# amebot_sensores.net
KiCad netlist of a schematic drawn in EAGLE
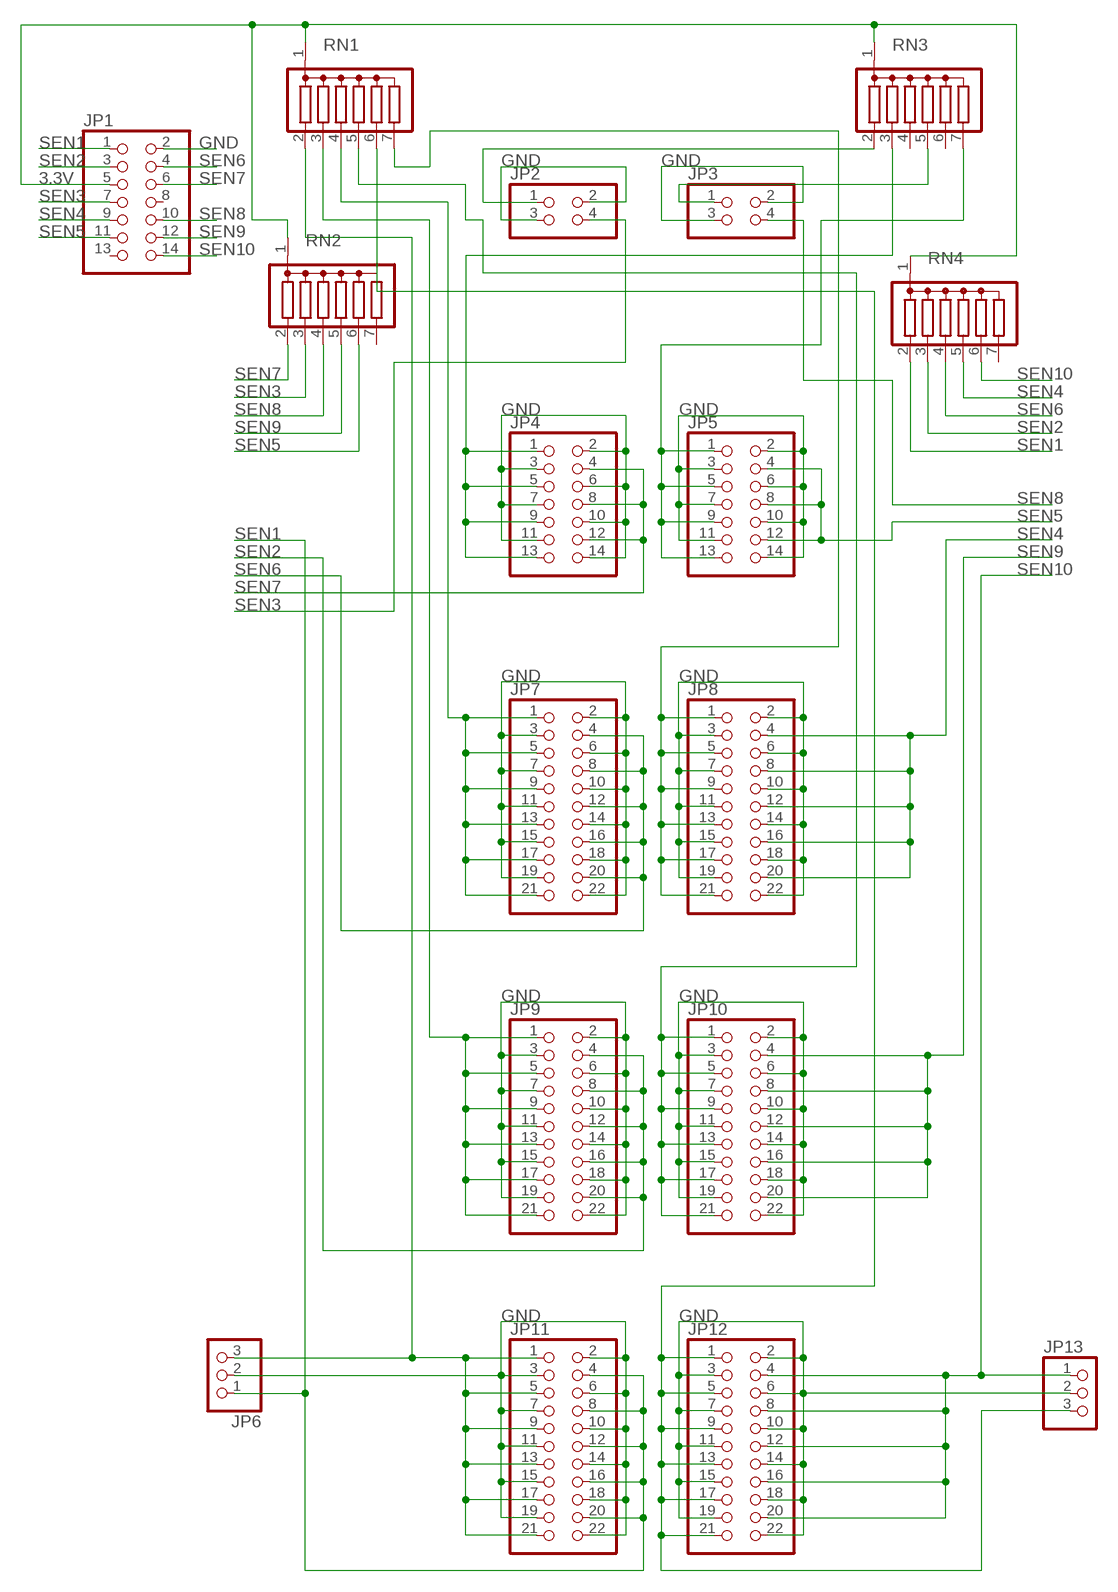
[diagram p0: schematic, sheet 1]

(export (version "E")
  (design (tool "Eeschema 10.0.6"))
  (components
    (comp (ref "JP1")
      (value "PINHD-2X7")
      (footprint "eagle-import:2X07")
      (libsource (lib "eagle-import") (part "PINHD-2X7"))
    )
    (comp (ref "JP2")
      (value "PINHD-2X2")
      (footprint "eagle-import:2X02")
      (libsource (lib "eagle-import") (part "PINHD-2X2"))
    )
    (comp (ref "JP3")
      (value "PINHD-2X2")
      (footprint "eagle-import:2X02")
      (libsource (lib "eagle-import") (part "PINHD-2X2"))
    )
    (comp (ref "JP4")
      (value "PINHD-2X7")
      (footprint "eagle-import:2X07")
      (libsource (lib "eagle-import") (part "PINHD-2X7"))
    )
    (comp (ref "JP5")
      (value "PINHD-2X7")
      (footprint "eagle-import:2X07")
      (libsource (lib "eagle-import") (part "PINHD-2X7"))
    )
    (comp (ref "JP6")
      (value "PINHD-1X3")
      (footprint "eagle-import:1X03")
      (libsource (lib "eagle-import") (part "PINHD-1X3"))
    )
    (comp (ref "JP7")
      (value "PINHD-2X11")
      (footprint "eagle-import:2X11")
      (libsource (lib "eagle-import") (part "PINHD-2X11"))
    )
    (comp (ref "JP8")
      (value "PINHD-2X11")
      (footprint "eagle-import:2X11")
      (libsource (lib "eagle-import") (part "PINHD-2X11"))
    )
    (comp (ref "JP9")
      (value "PINHD-2X11")
      (footprint "eagle-import:2X11")
      (libsource (lib "eagle-import") (part "PINHD-2X11"))
    )
    (comp (ref "JP10")
      (value "PINHD-2X11")
      (footprint "eagle-import:2X11")
      (libsource (lib "eagle-import") (part "PINHD-2X11"))
    )
    (comp (ref "JP11")
      (value "PINHD-2X11")
      (footprint "eagle-import:2X11")
      (libsource (lib "eagle-import") (part "PINHD-2X11"))
    )
    (comp (ref "JP12")
      (value "PINHD-2X11")
      (footprint "eagle-import:2X11")
      (libsource (lib "eagle-import") (part "PINHD-2X11"))
    )
    (comp (ref "JP13")
      (value "PINHD-1X3")
      (footprint "eagle-import:1X03")
      (libsource (lib "eagle-import") (part "PINHD-1X3"))
    )
    (comp (ref "RN1")
      (value "G06R")
      (footprint "eagle-import:SIL7")
      (libsource (lib "eagle-import") (part "G06R"))
    )
    (comp (ref "RN2")
      (value "G06R")
      (footprint "eagle-import:SIL7")
      (libsource (lib "eagle-import") (part "G06R"))
    )
    (comp (ref "RN3")
      (value "G06R")
      (footprint "eagle-import:SIL7")
      (libsource (lib "eagle-import") (part "G06R"))
    )
    (comp (ref "RN4")
      (value "G06R")
      (footprint "eagle-import:SIL7")
      (libsource (lib "eagle-import") (part "G06R"))
    )
  )
  (nets
    (net (code "1") (name "/3.3V") (class "Default")
      (node (ref "JP1") (pin "5") (pinfunction "5_5") (pintype "passive"))
      (node (ref "RN1") (pin "1") (pinfunction "1_1") (pintype "passive"))
      (node (ref "RN2") (pin "1") (pinfunction "1_1") (pintype "passive"))
      (node (ref "RN3") (pin "1") (pinfunction "1_1") (pintype "passive"))
      (node (ref "RN4") (pin "1") (pinfunction "1_1") (pintype "passive"))
    )
    (net (code "2") (name "/GND") (class "Default")
      (node (ref "JP1") (pin "2") (pinfunction "2_2") (pintype "passive"))
      (node (ref "JP10") (pin "10") (pinfunction "10_10") (pintype "passive"))
      (node (ref "JP10") (pin "11") (pinfunction "11_11") (pintype "passive"))
      (node (ref "JP10") (pin "14") (pinfunction "14_14") (pintype "passive"))
      (node (ref "JP10") (pin "15") (pinfunction "15_15") (pintype "passive"))
      (node (ref "JP10") (pin "18") (pinfunction "18_18") (pintype "passive"))
      (node (ref "JP10") (pin "19") (pinfunction "19_19") (pintype "passive"))
      (node (ref "JP10") (pin "2") (pinfunction "2_2") (pintype "passive"))
      (node (ref "JP10") (pin "22") (pinfunction "22_22") (pintype "passive"))
      (node (ref "JP10") (pin "3") (pinfunction "3_3") (pintype "passive"))
      (node (ref "JP10") (pin "6") (pinfunction "6_6") (pintype "passive"))
      (node (ref "JP10") (pin "7") (pinfunction "7_7") (pintype "passive"))
      (node (ref "JP11") (pin "10") (pinfunction "10_10") (pintype "passive"))
      (node (ref "JP11") (pin "11") (pinfunction "11_11") (pintype "passive"))
      (node (ref "JP11") (pin "14") (pinfunction "14_14") (pintype "passive"))
      (node (ref "JP11") (pin "15") (pinfunction "15_15") (pintype "passive"))
      (node (ref "JP11") (pin "18") (pinfunction "18_18") (pintype "passive"))
      (node (ref "JP11") (pin "19") (pinfunction "19_19") (pintype "passive"))
      (node (ref "JP11") (pin "2") (pinfunction "2_2") (pintype "passive"))
      (node (ref "JP11") (pin "22") (pinfunction "22_22") (pintype "passive"))
      (node (ref "JP11") (pin "3") (pinfunction "3_3") (pintype "passive"))
      (node (ref "JP11") (pin "6") (pinfunction "6_6") (pintype "passive"))
      (node (ref "JP11") (pin "7") (pinfunction "7_7") (pintype "passive"))
      (node (ref "JP12") (pin "10") (pinfunction "10_10") (pintype "passive"))
      (node (ref "JP12") (pin "11") (pinfunction "11_11") (pintype "passive"))
      (node (ref "JP12") (pin "14") (pinfunction "14_14") (pintype "passive"))
      (node (ref "JP12") (pin "15") (pinfunction "15_15") (pintype "passive"))
      (node (ref "JP12") (pin "18") (pinfunction "18_18") (pintype "passive"))
      (node (ref "JP12") (pin "19") (pinfunction "19_19") (pintype "passive"))
      (node (ref "JP12") (pin "2") (pinfunction "2_2") (pintype "passive"))
      (node (ref "JP12") (pin "22") (pinfunction "22_22") (pintype "passive"))
      (node (ref "JP12") (pin "3") (pinfunction "3_3") (pintype "passive"))
      (node (ref "JP12") (pin "6") (pinfunction "6_6") (pintype "passive"))
      (node (ref "JP12") (pin "7") (pinfunction "7_7") (pintype "passive"))
      (node (ref "JP13") (pin "2") (pinfunction "2_2") (pintype "passive"))
      (node (ref "JP2") (pin "2") (pinfunction "2_2") (pintype "passive"))
      (node (ref "JP2") (pin "3") (pinfunction "3_3") (pintype "passive"))
      (node (ref "JP3") (pin "2") (pinfunction "2_2") (pintype "passive"))
      (node (ref "JP3") (pin "3") (pinfunction "3_3") (pintype "passive"))
      (node (ref "JP4") (pin "10") (pinfunction "10_10") (pintype "passive"))
      (node (ref "JP4") (pin "11") (pinfunction "11_11") (pintype "passive"))
      (node (ref "JP4") (pin "14") (pinfunction "14_14") (pintype "passive"))
      (node (ref "JP4") (pin "2") (pinfunction "2_2") (pintype "passive"))
      (node (ref "JP4") (pin "3") (pinfunction "3_3") (pintype "passive"))
      (node (ref "JP4") (pin "6") (pinfunction "6_6") (pintype "passive"))
      (node (ref "JP4") (pin "7") (pinfunction "7_7") (pintype "passive"))
      (node (ref "JP5") (pin "10") (pinfunction "10_10") (pintype "passive"))
      (node (ref "JP5") (pin "11") (pinfunction "11_11") (pintype "passive"))
      (node (ref "JP5") (pin "14") (pinfunction "14_14") (pintype "passive"))
      (node (ref "JP5") (pin "2") (pinfunction "2_2") (pintype "passive"))
      (node (ref "JP5") (pin "3") (pinfunction "3_3") (pintype "passive"))
      (node (ref "JP5") (pin "6") (pinfunction "6_6") (pintype "passive"))
      (node (ref "JP5") (pin "7") (pinfunction "7_7") (pintype "passive"))
      (node (ref "JP6") (pin "2") (pinfunction "2_2") (pintype "passive"))
      (node (ref "JP7") (pin "10") (pinfunction "10_10") (pintype "passive"))
      (node (ref "JP7") (pin "11") (pinfunction "11_11") (pintype "passive"))
      (node (ref "JP7") (pin "14") (pinfunction "14_14") (pintype "passive"))
      (node (ref "JP7") (pin "15") (pinfunction "15_15") (pintype "passive"))
      (node (ref "JP7") (pin "18") (pinfunction "18_18") (pintype "passive"))
      (node (ref "JP7") (pin "19") (pinfunction "19_19") (pintype "passive"))
      (node (ref "JP7") (pin "2") (pinfunction "2_2") (pintype "passive"))
      (node (ref "JP7") (pin "22") (pinfunction "22_22") (pintype "passive"))
      (node (ref "JP7") (pin "3") (pinfunction "3_3") (pintype "passive"))
      (node (ref "JP7") (pin "6") (pinfunction "6_6") (pintype "passive"))
      (node (ref "JP7") (pin "7") (pinfunction "7_7") (pintype "passive"))
      (node (ref "JP8") (pin "10") (pinfunction "10_10") (pintype "passive"))
      (node (ref "JP8") (pin "11") (pinfunction "11_11") (pintype "passive"))
      (node (ref "JP8") (pin "14") (pinfunction "14_14") (pintype "passive"))
      (node (ref "JP8") (pin "15") (pinfunction "15_15") (pintype "passive"))
      (node (ref "JP8") (pin "18") (pinfunction "18_18") (pintype "passive"))
      (node (ref "JP8") (pin "19") (pinfunction "19_19") (pintype "passive"))
      (node (ref "JP8") (pin "2") (pinfunction "2_2") (pintype "passive"))
      (node (ref "JP8") (pin "22") (pinfunction "22_22") (pintype "passive"))
      (node (ref "JP8") (pin "3") (pinfunction "3_3") (pintype "passive"))
      (node (ref "JP8") (pin "6") (pinfunction "6_6") (pintype "passive"))
      (node (ref "JP8") (pin "7") (pinfunction "7_7") (pintype "passive"))
      (node (ref "JP9") (pin "10") (pinfunction "10_10") (pintype "passive"))
      (node (ref "JP9") (pin "11") (pinfunction "11_11") (pintype "passive"))
      (node (ref "JP9") (pin "14") (pinfunction "14_14") (pintype "passive"))
      (node (ref "JP9") (pin "15") (pinfunction "15_15") (pintype "passive"))
      (node (ref "JP9") (pin "18") (pinfunction "18_18") (pintype "passive"))
      (node (ref "JP9") (pin "19") (pinfunction "19_19") (pintype "passive"))
      (node (ref "JP9") (pin "2") (pinfunction "2_2") (pintype "passive"))
      (node (ref "JP9") (pin "22") (pinfunction "22_22") (pintype "passive"))
      (node (ref "JP9") (pin "3") (pinfunction "3_3") (pintype "passive"))
      (node (ref "JP9") (pin "6") (pinfunction "6_6") (pintype "passive"))
      (node (ref "JP9") (pin "7") (pinfunction "7_7") (pintype "passive"))
    )
    (net (code "3") (name "/SEN1") (class "Default")
      (node (ref "JP1") (pin "1") (pinfunction "1_1") (pintype "passive"))
      (node (ref "JP11") (pin "12") (pinfunction "12_12") (pintype "passive"))
      (node (ref "JP11") (pin "16") (pinfunction "16_16") (pintype "passive"))
      (node (ref "JP11") (pin "20") (pinfunction "20_20") (pintype "passive"))
      (node (ref "JP11") (pin "4") (pinfunction "4_4") (pintype "passive"))
      (node (ref "JP11") (pin "8") (pinfunction "8_8") (pintype "passive"))
      (node (ref "JP6") (pin "1") (pinfunction "1_1") (pintype "passive"))
      (node (ref "RN4") (pin "2") (pinfunction "2_2") (pintype "passive"))
    )
    (net (code "4") (name "/SEN2") (class "Default")
      (node (ref "JP1") (pin "3") (pinfunction "3_3") (pintype "passive"))
      (node (ref "JP9") (pin "12") (pinfunction "12_12") (pintype "passive"))
      (node (ref "JP9") (pin "16") (pinfunction "16_16") (pintype "passive"))
      (node (ref "JP9") (pin "20") (pinfunction "20_20") (pintype "passive"))
      (node (ref "JP9") (pin "4") (pinfunction "4_4") (pintype "passive"))
      (node (ref "JP9") (pin "8") (pinfunction "8_8") (pintype "passive"))
      (node (ref "RN4") (pin "3") (pinfunction "3_3") (pintype "passive"))
    )
    (net (code "5") (name "/SEN3") (class "Default")
      (node (ref "JP1") (pin "7") (pinfunction "7_7") (pintype "passive"))
      (node (ref "JP2") (pin "4") (pinfunction "4_4") (pintype "passive"))
      (node (ref "RN2") (pin "3") (pinfunction "3_3") (pintype "passive"))
    )
    (net (code "6") (name "/SEN4") (class "Default")
      (node (ref "JP1") (pin "9") (pinfunction "9_9") (pintype "passive"))
      (node (ref "JP8") (pin "12") (pinfunction "12_12") (pintype "passive"))
      (node (ref "JP8") (pin "16") (pinfunction "16_16") (pintype "passive"))
      (node (ref "JP8") (pin "20") (pinfunction "20_20") (pintype "passive"))
      (node (ref "JP8") (pin "4") (pinfunction "4_4") (pintype "passive"))
      (node (ref "JP8") (pin "8") (pinfunction "8_8") (pintype "passive"))
      (node (ref "RN4") (pin "5") (pinfunction "5_5") (pintype "passive"))
    )
    (net (code "7") (name "/SEN5") (class "Default")
      (node (ref "JP1") (pin "11") (pinfunction "11_11") (pintype "passive"))
      (node (ref "JP5") (pin "12") (pinfunction "12_12") (pintype "passive"))
      (node (ref "JP5") (pin "4") (pinfunction "4_4") (pintype "passive"))
      (node (ref "JP5") (pin "8") (pinfunction "8_8") (pintype "passive"))
      (node (ref "RN2") (pin "6") (pinfunction "6_6") (pintype "passive"))
    )
    (net (code "8") (name "/SEN6") (class "Default")
      (node (ref "JP1") (pin "4") (pinfunction "4_4") (pintype "passive"))
      (node (ref "JP7") (pin "12") (pinfunction "12_12") (pintype "passive"))
      (node (ref "JP7") (pin "16") (pinfunction "16_16") (pintype "passive"))
      (node (ref "JP7") (pin "20") (pinfunction "20_20") (pintype "passive"))
      (node (ref "JP7") (pin "4") (pinfunction "4_4") (pintype "passive"))
      (node (ref "JP7") (pin "8") (pinfunction "8_8") (pintype "passive"))
      (node (ref "RN4") (pin "4") (pinfunction "4_4") (pintype "passive"))
    )
    (net (code "9") (name "/SEN7") (class "Default")
      (node (ref "JP1") (pin "6") (pinfunction "6_6") (pintype "passive"))
      (node (ref "JP4") (pin "12") (pinfunction "12_12") (pintype "passive"))
      (node (ref "JP4") (pin "4") (pinfunction "4_4") (pintype "passive"))
      (node (ref "JP4") (pin "8") (pinfunction "8_8") (pintype "passive"))
      (node (ref "RN2") (pin "2") (pinfunction "2_2") (pintype "passive"))
    )
    (net (code "10") (name "/SEN8") (class "Default")
      (node (ref "JP1") (pin "10") (pinfunction "10_10") (pintype "passive"))
      (node (ref "JP3") (pin "4") (pinfunction "4_4") (pintype "passive"))
      (node (ref "RN2") (pin "4") (pinfunction "4_4") (pintype "passive"))
    )
    (net (code "11") (name "/SEN9") (class "Default")
      (node (ref "JP1") (pin "12") (pinfunction "12_12") (pintype "passive"))
      (node (ref "JP10") (pin "12") (pinfunction "12_12") (pintype "passive"))
      (node (ref "JP10") (pin "16") (pinfunction "16_16") (pintype "passive"))
      (node (ref "JP10") (pin "20") (pinfunction "20_20") (pintype "passive"))
      (node (ref "JP10") (pin "4") (pinfunction "4_4") (pintype "passive"))
      (node (ref "JP10") (pin "8") (pinfunction "8_8") (pintype "passive"))
      (node (ref "RN2") (pin "5") (pinfunction "5_5") (pintype "passive"))
    )
    (net (code "12") (name "/SEN10") (class "Default")
      (node (ref "JP1") (pin "14") (pinfunction "14_14") (pintype "passive"))
      (node (ref "JP12") (pin "12") (pinfunction "12_12") (pintype "passive"))
      (node (ref "JP12") (pin "16") (pinfunction "16_16") (pintype "passive"))
      (node (ref "JP12") (pin "20") (pinfunction "20_20") (pintype "passive"))
      (node (ref "JP12") (pin "4") (pinfunction "4_4") (pintype "passive"))
      (node (ref "JP12") (pin "8") (pinfunction "8_8") (pintype "passive"))
      (node (ref "JP13") (pin "1") (pinfunction "1_1") (pintype "passive"))
      (node (ref "RN4") (pin "6") (pinfunction "6_6") (pintype "passive"))
    )
    (net (code "13") (name "Net-(JP2-Pad1)") (class "Default")
      (node (ref "JP2") (pin "1") (pinfunction "1_1") (pintype "passive"))
      (node (ref "RN3") (pin "2") (pinfunction "2_2") (pintype "passive"))
    )
    (net (code "14") (name "Net-(JP3-Pad1)") (class "Default")
      (node (ref "JP3") (pin "1") (pinfunction "1_1") (pintype "passive"))
      (node (ref "RN3") (pin "5") (pinfunction "5_5") (pintype "passive"))
    )
    (net (code "15") (name "Net-(JP4-Pad1)") (class "Default")
      (node (ref "JP4") (pin "1") (pinfunction "1_1") (pintype "passive"))
      (node (ref "JP4") (pin "13") (pinfunction "13_13") (pintype "passive"))
      (node (ref "JP4") (pin "5") (pinfunction "5_5") (pintype "passive"))
      (node (ref "JP4") (pin "9") (pinfunction "9_9") (pintype "passive"))
      (node (ref "RN3") (pin "3") (pinfunction "3_3") (pintype "passive"))
    )
    (net (code "16") (name "Net-(JP5-Pad1)") (class "Default")
      (node (ref "JP5") (pin "1") (pinfunction "1_1") (pintype "passive"))
      (node (ref "JP5") (pin "13") (pinfunction "13_13") (pintype "passive"))
      (node (ref "JP5") (pin "5") (pinfunction "5_5") (pintype "passive"))
      (node (ref "JP5") (pin "9") (pinfunction "9_9") (pintype "passive"))
      (node (ref "RN3") (pin "7") (pinfunction "7_7") (pintype "passive"))
    )
    (net (code "17") (name "Net-(JP7-Pad1)") (class "Default")
      (node (ref "JP7") (pin "1") (pinfunction "1_1") (pintype "passive"))
      (node (ref "JP7") (pin "13") (pinfunction "13_13") (pintype "passive"))
      (node (ref "JP7") (pin "17") (pinfunction "17_17") (pintype "passive"))
      (node (ref "JP7") (pin "21") (pinfunction "21_21") (pintype "passive"))
      (node (ref "JP7") (pin "5") (pinfunction "5_5") (pintype "passive"))
      (node (ref "JP7") (pin "9") (pinfunction "9_9") (pintype "passive"))
      (node (ref "RN1") (pin "4") (pinfunction "4_4") (pintype "passive"))
    )
    (net (code "18") (name "Net-(JP8-Pad1)") (class "Default")
      (node (ref "JP8") (pin "1") (pinfunction "1_1") (pintype "passive"))
      (node (ref "JP8") (pin "13") (pinfunction "13_13") (pintype "passive"))
      (node (ref "JP8") (pin "17") (pinfunction "17_17") (pintype "passive"))
      (node (ref "JP8") (pin "21") (pinfunction "21_21") (pintype "passive"))
      (node (ref "JP8") (pin "5") (pinfunction "5_5") (pintype "passive"))
      (node (ref "JP8") (pin "9") (pinfunction "9_9") (pintype "passive"))
      (node (ref "RN1") (pin "7") (pinfunction "7_7") (pintype "passive"))
    )
    (net (code "19") (name "Net-(JP9-Pad1)") (class "Default")
      (node (ref "JP9") (pin "1") (pinfunction "1_1") (pintype "passive"))
      (node (ref "JP9") (pin "13") (pinfunction "13_13") (pintype "passive"))
      (node (ref "JP9") (pin "17") (pinfunction "17_17") (pintype "passive"))
      (node (ref "JP9") (pin "21") (pinfunction "21_21") (pintype "passive"))
      (node (ref "JP9") (pin "5") (pinfunction "5_5") (pintype "passive"))
      (node (ref "JP9") (pin "9") (pinfunction "9_9") (pintype "passive"))
      (node (ref "RN1") (pin "3") (pinfunction "3_3") (pintype "passive"))
    )
    (net (code "20") (name "Net-(JP10-Pad1)") (class "Default")
      (node (ref "JP10") (pin "1") (pinfunction "1_1") (pintype "passive"))
      (node (ref "JP10") (pin "13") (pinfunction "13_13") (pintype "passive"))
      (node (ref "JP10") (pin "17") (pinfunction "17_17") (pintype "passive"))
      (node (ref "JP10") (pin "21") (pinfunction "21_21") (pintype "passive"))
      (node (ref "JP10") (pin "5") (pinfunction "5_5") (pintype "passive"))
      (node (ref "JP10") (pin "9") (pinfunction "9_9") (pintype "passive"))
      (node (ref "RN1") (pin "5") (pinfunction "5_5") (pintype "passive"))
    )
    (net (code "21") (name "Net-(JP11-Pad1)") (class "Default")
      (node (ref "JP11") (pin "1") (pinfunction "1_1") (pintype "passive"))
      (node (ref "JP11") (pin "13") (pinfunction "13_13") (pintype "passive"))
      (node (ref "JP11") (pin "17") (pinfunction "17_17") (pintype "passive"))
      (node (ref "JP11") (pin "21") (pinfunction "21_21") (pintype "passive"))
      (node (ref "JP11") (pin "5") (pinfunction "5_5") (pintype "passive"))
      (node (ref "JP11") (pin "9") (pinfunction "9_9") (pintype "passive"))
      (node (ref "JP6") (pin "3") (pinfunction "3_3") (pintype "passive"))
      (node (ref "RN1") (pin "2") (pinfunction "2_2") (pintype "passive"))
    )
    (net (code "22") (name "Net-(JP12-Pad1)") (class "Default")
      (node (ref "JP12") (pin "1") (pinfunction "1_1") (pintype "passive"))
      (node (ref "JP12") (pin "13") (pinfunction "13_13") (pintype "passive"))
      (node (ref "JP12") (pin "17") (pinfunction "17_17") (pintype "passive"))
      (node (ref "JP12") (pin "21") (pinfunction "21_21") (pintype "passive"))
      (node (ref "JP12") (pin "5") (pinfunction "5_5") (pintype "passive"))
      (node (ref "JP12") (pin "9") (pinfunction "9_9") (pintype "passive"))
      (node (ref "JP13") (pin "3") (pinfunction "3_3") (pintype "passive"))
      (node (ref "RN1") (pin "6") (pinfunction "6_6") (pintype "passive"))
    )
    (net (code "23") (name "unconnected-(JP1-Pad8)") (class "Default")
      (node (ref "JP1") (pin "8") (pinfunction "8_8") (pintype "passive"))
    )
    (net (code "24") (name "unconnected-(JP1-Pad13)") (class "Default")
      (node (ref "JP1") (pin "13") (pinfunction "13_13") (pintype "passive"))
    )
    (net (code "25") (name "unconnected-(RN2-Pad7)") (class "Default")
      (node (ref "RN2") (pin "7") (pinfunction "7_7") (pintype "passive"))
    )
    (net (code "26") (name "unconnected-(RN3-Pad4)") (class "Default")
      (node (ref "RN3") (pin "4") (pinfunction "4_4") (pintype "passive"))
    )
    (net (code "27") (name "unconnected-(RN3-Pad6)") (class "Default")
      (node (ref "RN3") (pin "6") (pinfunction "6_6") (pintype "passive"))
    )
    (net (code "28") (name "unconnected-(RN4-Pad7)") (class "Default")
      (node (ref "RN4") (pin "7") (pinfunction "7_7") (pintype "passive"))
    )
  )
)
